# E-Book_Reader.net
KiCad netlist of a schematic drawn in EAGLE
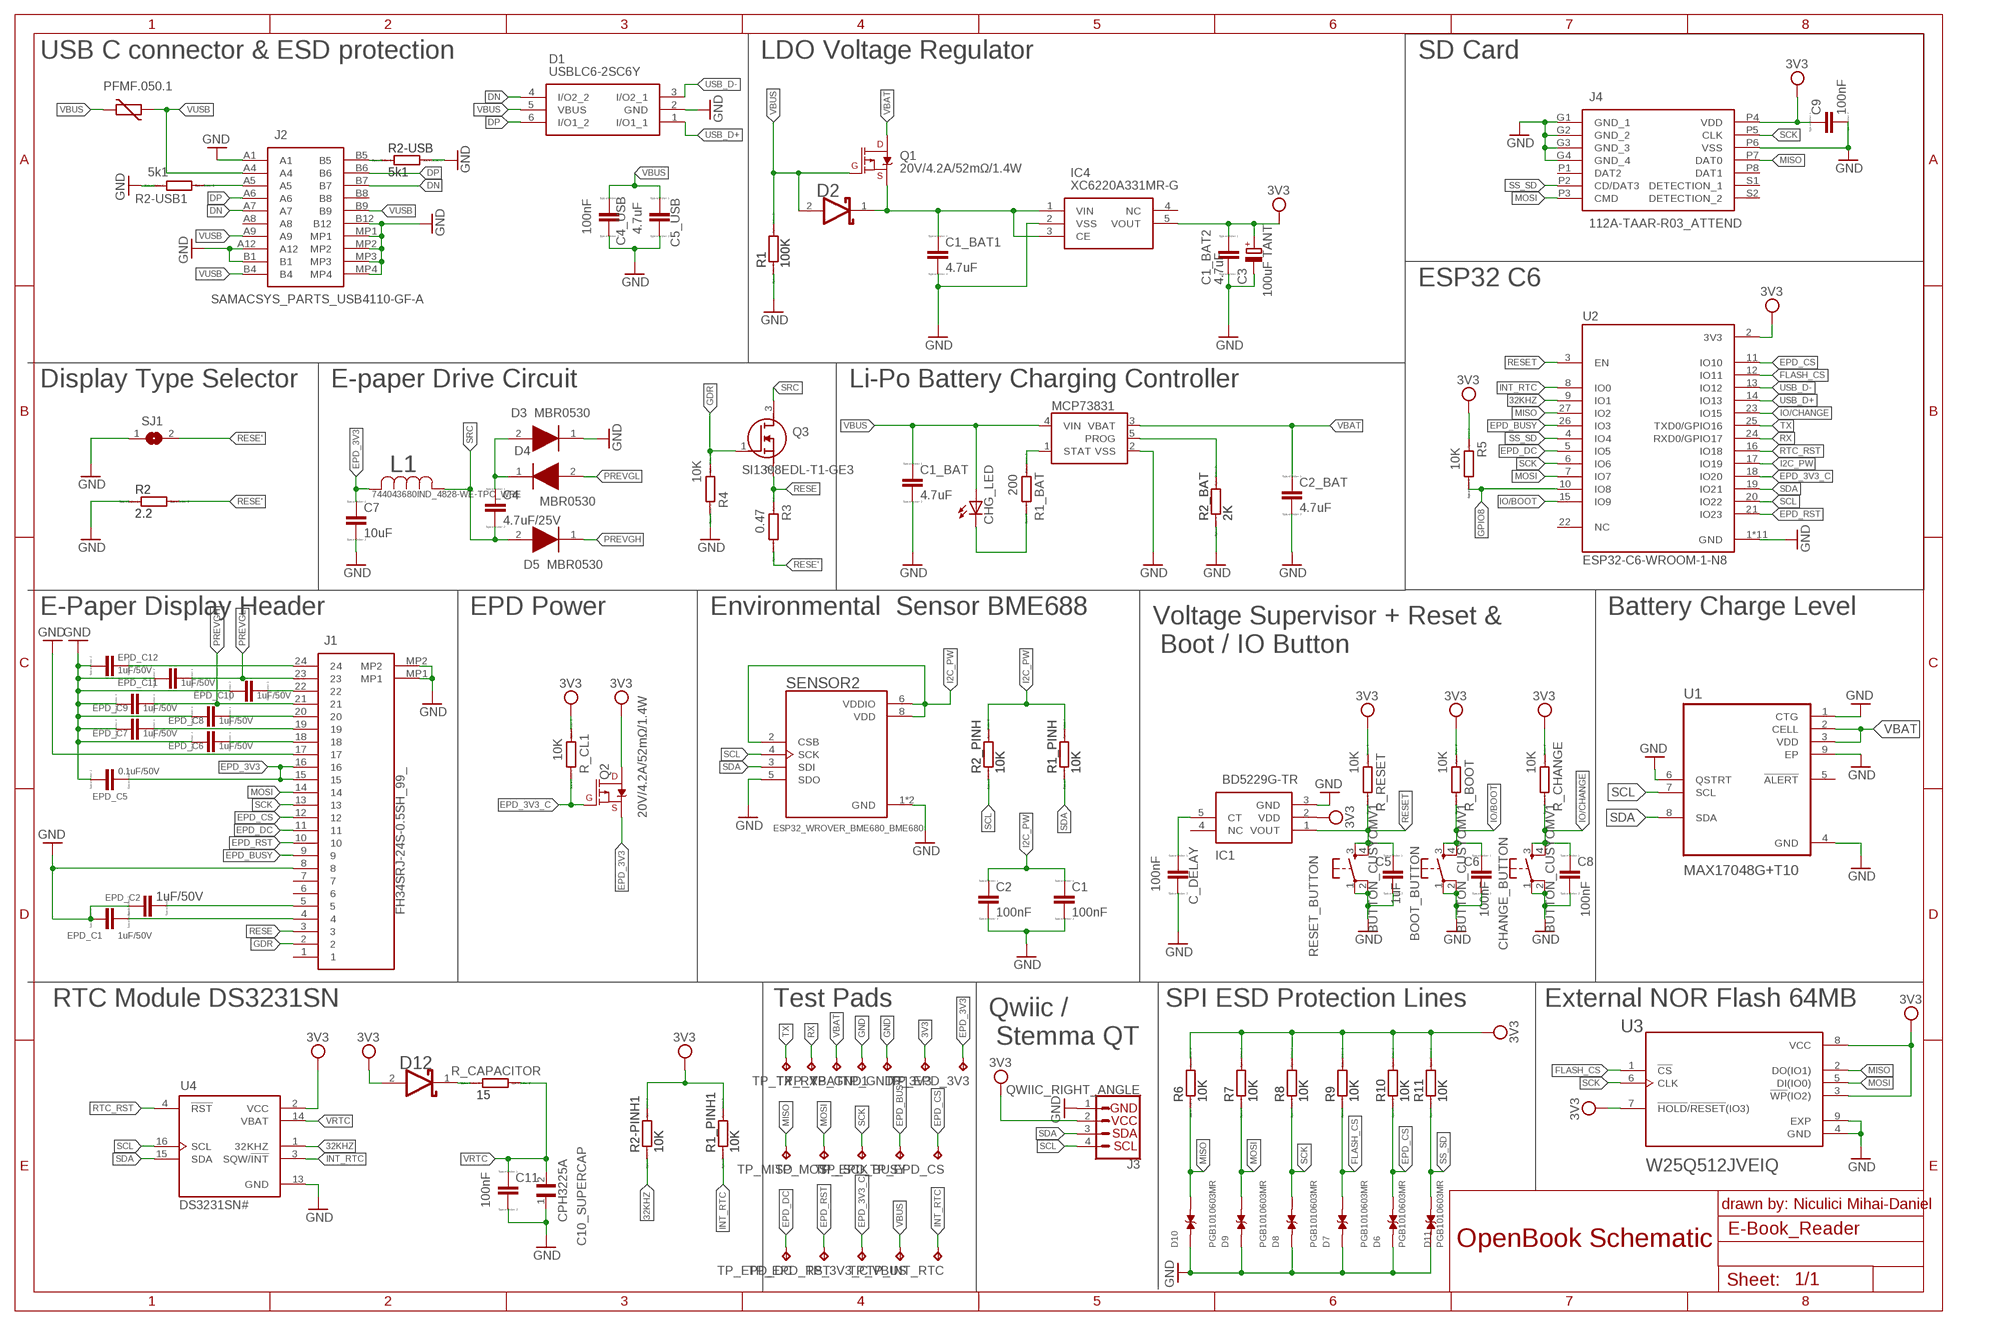
[diagram p0: schematic, sheet 1]

(export (version "E")
  (design (tool "Eeschema 10.0.6"))
  (components
    (comp (ref "BOOT_BUTTON")
      (value "BUTTON_CUSYOMV1")
      (footprint "eagle-import:MYBUTTON")
      (libsource (lib "eagle-import") (part "BUTTON_CUSYOMV1"))
    )
    (comp (ref "C1")
      (value "100nF")
      (footprint "eagle-import:ESP32_WROVER_EAGLE-LTSPICE_C0402")
      (libsource (lib "eagle-import") (part "EAGLE-LTSPICE_CC0402"))
    )
    (comp (ref "C1_BAT")
      (value "4.7uF")
      (footprint "eagle-import:ESP32_WROVER_EAGLE-LTSPICE_C0402")
      (libsource (lib "eagle-import") (part "ESP32_WROVER_EAGLE-LTSPICE_CC0402"))
    )
    (comp (ref "C1_BAT1")
      (value "4.7uF")
      (footprint "eagle-import:ESP32_WROVER_EAGLE-LTSPICE_C0402")
      (libsource (lib "eagle-import") (part "EAGLE-LTSPICE_CC0402"))
    )
    (comp (ref "C1_BAT2")
      (value "4.7uF")
      (footprint "eagle-import:ESP32_WROVER_EAGLE-LTSPICE_C0402")
      (libsource (lib "eagle-import") (part "ESP32_WROVER_EAGLE-LTSPICE_CC0402"))
    )
    (comp (ref "C2")
      (value "100nF")
      (footprint "eagle-import:ESP32_WROVER_EAGLE-LTSPICE_C0402")
      (libsource (lib "eagle-import") (part "EAGLE-LTSPICE_CC0402"))
    )
    (comp (ref "C2_BAT")
      (value "4.7uF")
      (footprint "eagle-import:ESP32_WROVER_EAGLE-LTSPICE_C0402")
      (libsource (lib "eagle-import") (part "ESP32_WROVER_EAGLE-LTSPICE_CC0402"))
    )
    (comp (ref "C3")
      (value "100uF TANT")
      (footprint "eagle-import:RCL_CT3528")
      (libsource (lib "eagle-import") (part "RCL_CPOL-EUCT3528"))
    )
    (comp (ref "C4")
      (value "4.7uF/25V")
      (footprint "eagle-import:ESP32_WROVER_EAGLE-LTSPICE_C0402")
      (libsource (lib "eagle-import") (part "ESP32_WROVER_EAGLE-LTSPICE_CC0402"))
    )
    (comp (ref "C4_USB")
      (value "100nF")
      (footprint "eagle-import:ESP32_WROVER_EAGLE-LTSPICE_C0402")
      (libsource (lib "eagle-import") (part "EAGLE-LTSPICE_CC0402"))
    )
    (comp (ref "C5")
      (value "1uF")
      (footprint "eagle-import:ESP32_WROVER_EAGLE-LTSPICE_C0402")
      (libsource (lib "eagle-import") (part "EAGLE-LTSPICE_CC0402"))
    )
    (comp (ref "C5_USB")
      (value "4.7uF")
      (footprint "eagle-import:ESP32_WROVER_EAGLE-LTSPICE_C0402")
      (libsource (lib "eagle-import") (part "EAGLE-LTSPICE_CC0402"))
    )
    (comp (ref "C6")
      (value "100nF")
      (footprint "eagle-import:ESP32_WROVER_EAGLE-LTSPICE_C0402")
      (libsource (lib "eagle-import") (part "EAGLE-LTSPICE_CC0402"))
    )
    (comp (ref "C7")
      (value "10uF")
      (footprint "eagle-import:ESP32_WROVER_EAGLE-LTSPICE_C0402")
      (libsource (lib "eagle-import") (part "EAGLE-LTSPICE_CC0402"))
    )
    (comp (ref "C8")
      (value "100nF")
      (footprint "eagle-import:ESP32_WROVER_EAGLE-LTSPICE_C0402")
      (libsource (lib "eagle-import") (part "EAGLE-LTSPICE_CC0402"))
    )
    (comp (ref "C9")
      (value "100nF")
      (footprint "eagle-import:ESP32_WROVER_EAGLE-LTSPICE_C0402")
      (libsource (lib "eagle-import") (part "EAGLE-LTSPICE_CC0402"))
    )
    (comp (ref "C10_SUPERCAP")
      (value "CPH3225A")
      (footprint "eagle-import:CAPCP3225X100N")
      (fields (field (name "MF") "Seiko Instruments"))
      (libsource (lib "eagle-import") (part "CPH3225A"))
    )
    (comp (ref "C11")
      (value "100nF")
      (footprint "eagle-import:ESP32_WROVER_EAGLE-LTSPICE_C0402")
      (libsource (lib "eagle-import") (part "EAGLE-LTSPICE_CC0402"))
    )
    (comp (ref "CHANGE_BUTTON")
      (value "BUTTON_CUSYOMV1")
      (footprint "eagle-import:MYBUTTON")
      (libsource (lib "eagle-import") (part "BUTTON_CUSYOMV1"))
    )
    (comp (ref "CHG_LED")
      (value "ADAFRUIT_LEDCHIP-LED0603")
      (footprint "eagle-import:ADAFRUIT_CHIP-LED0603")
      (libsource (lib "eagle-import") (part "ADAFRUIT_LEDCHIP-LED0603"))
    )
    (comp (ref "C_DELAY")
      (value "100nF")
      (footprint "eagle-import:ESP32_WROVER_EAGLE-LTSPICE_C0402")
      (libsource (lib "eagle-import") (part "EAGLE-LTSPICE_CC0402"))
    )
    (comp (ref "D1")
      (value "USBLC6-2SC6Y")
      (footprint "eagle-import:SOT95P280X145-6N")
      (fields (field (name "MF") "STMicroelectronics"))
      (libsource (lib "eagle-import") (part "USBLC6-2SC6Y"))
    )
    (comp (ref "D2")
      (value "ESP32_WROVER_AVX---SD0805S020S1R0_AVX_SD0805S020S1R0_0_0AVX_SD0805S020S1R0_0_0")
      (footprint "eagle-import:ESP32_WROVER_AVX---SD0805S020S1R0_AVX_SD0805S020S1R0_0")
      (fields
        (field (name "DIGIKEY_PART_NUMBER") "478-7800-1-ND")
        (field (name "MF") "AVX")
        (field (name "MOUSER_PART_NUMBER") "581-SD0805S020S1R0")
      )
      (libsource (lib "eagle-import") (part "ESP32_WROVER_AVX---SD0805S020S1R0_AVX_SD0805S020S1R0_0_0AVX_SD0805S020S1R0_0_0"))
    )
    (comp (ref "D3")
      (value "MBR0530")
      (footprint "eagle-import:SOD3716X135N")
      (fields (field (name "MF") "ON Semiconductor"))
      (libsource (lib "eagle-import") (part "MBR0530"))
    )
    (comp (ref "D4")
      (value "MBR0530")
      (footprint "eagle-import:SOD3716X135N")
      (fields (field (name "MF") "ON Semiconductor"))
      (libsource (lib "eagle-import") (part "MBR0530"))
    )
    (comp (ref "D5")
      (value "MBR0530")
      (footprint "eagle-import:SOD3716X135N")
      (fields (field (name "MF") "ON Semiconductor"))
      (libsource (lib "eagle-import") (part "MBR0530"))
    )
    (comp (ref "D6")
      (value "PGB1010603MR")
      (footprint "eagle-import:DIOC1608X36N")
      (fields (field (name "MF") "Littelfuse Inc."))
      (libsource (lib "eagle-import") (part "PGB1010603MR"))
    )
    (comp (ref "D7")
      (value "PGB1010603MR")
      (footprint "eagle-import:DIOC1608X36N")
      (fields (field (name "MF") "Littelfuse Inc."))
      (libsource (lib "eagle-import") (part "PGB1010603MR"))
    )
    (comp (ref "D8")
      (value "PGB1010603MR")
      (footprint "eagle-import:DIOC1608X36N")
      (fields (field (name "MF") "Littelfuse Inc."))
      (libsource (lib "eagle-import") (part "PGB1010603MR"))
    )
    (comp (ref "D9")
      (value "PGB1010603MR")
      (footprint "eagle-import:DIOC1608X36N")
      (fields (field (name "MF") "Littelfuse Inc."))
      (libsource (lib "eagle-import") (part "PGB1010603MR"))
    )
    (comp (ref "D10")
      (value "PGB1010603MR")
      (footprint "eagle-import:DIOC1608X36N")
      (fields (field (name "MF") "Littelfuse Inc."))
      (libsource (lib "eagle-import") (part "PGB1010603MR"))
    )
    (comp (ref "D11")
      (value "PGB1010603MR")
      (footprint "eagle-import:DIOC1608X36N")
      (fields (field (name "MF") "Littelfuse Inc."))
      (libsource (lib "eagle-import") (part "PGB1010603MR"))
    )
    (comp (ref "D12")
      (value "ESP32_WROVER_AVX---SD0805S020S1R0_AVX_SD0805S020S1R0_0_0AVX_SD0805S020S1R0_0_0")
      (footprint "eagle-import:ESP32_WROVER_AVX---SD0805S020S1R0_AVX_SD0805S020S1R0_0")
      (fields
        (field (name "DIGIKEY_PART_NUMBER") "478-7800-1-ND")
        (field (name "MF") "AVX")
        (field (name "MOUSER_PART_NUMBER") "581-SD0805S020S1R0")
      )
      (libsource (lib "eagle-import") (part "ESP32_WROVER_AVX---SD0805S020S1R0_AVX_SD0805S020S1R0_0_0AVX_SD0805S020S1R0_0_0"))
    )
    (comp (ref "EPD_C1")
      (value "1uF/50V")
      (footprint "eagle-import:ESP32_WROVER_EAGLE-LTSPICE_C0402")
      (libsource (lib "eagle-import") (part "EAGLE-LTSPICE_CC0402"))
    )
    (comp (ref "EPD_C2")
      (value "1uF/50V")
      (footprint "eagle-import:ESP32_WROVER_EAGLE-LTSPICE_C0402")
      (libsource (lib "eagle-import") (part "EAGLE-LTSPICE_CC0402"))
    )
    (comp (ref "EPD_C5")
      (value "0.1uF/50V")
      (footprint "eagle-import:ESP32_WROVER_EAGLE-LTSPICE_C0402")
      (libsource (lib "eagle-import") (part "EAGLE-LTSPICE_CC0402"))
    )
    (comp (ref "EPD_C6")
      (value "1uF/50V")
      (footprint "eagle-import:ESP32_WROVER_EAGLE-LTSPICE_C0402")
      (libsource (lib "eagle-import") (part "EAGLE-LTSPICE_CC0402"))
    )
    (comp (ref "EPD_C7")
      (value "1uF/50V")
      (footprint "eagle-import:ESP32_WROVER_EAGLE-LTSPICE_C0402")
      (libsource (lib "eagle-import") (part "EAGLE-LTSPICE_CC0402"))
    )
    (comp (ref "EPD_C8")
      (value "1uF/50V")
      (footprint "eagle-import:ESP32_WROVER_EAGLE-LTSPICE_C0402")
      (libsource (lib "eagle-import") (part "EAGLE-LTSPICE_CC0402"))
    )
    (comp (ref "EPD_C9")
      (value "1uF/50V")
      (footprint "eagle-import:ESP32_WROVER_EAGLE-LTSPICE_C0402")
      (libsource (lib "eagle-import") (part "EAGLE-LTSPICE_CC0402"))
    )
    (comp (ref "EPD_C10")
      (value "1uF/50V")
      (footprint "eagle-import:ESP32_WROVER_EAGLE-LTSPICE_C0402")
      (libsource (lib "eagle-import") (part "EAGLE-LTSPICE_CC0402"))
    )
    (comp (ref "EPD_C11")
      (value "1uF/50V")
      (footprint "eagle-import:ESP32_WROVER_EAGLE-LTSPICE_C0402")
      (libsource (lib "eagle-import") (part "EAGLE-LTSPICE_CC0402"))
    )
    (comp (ref "EPD_C12")
      (value "1uF/50V")
      (footprint "eagle-import:ESP32_WROVER_EAGLE-LTSPICE_C0402")
      (libsource (lib "eagle-import") (part "EAGLE-LTSPICE_CC0402"))
    )
    (comp (ref "IC1")
      (value "BD5229G-TR")
      (footprint "eagle-import:SOT95P280X125-5N")
      (fields (field (name "MOUSER_PART_NUMBER") "755-BD5229G-TR"))
      (libsource (lib "eagle-import") (part "BD5229G-TR"))
    )
    (comp (ref "IC4")
      (value "XC6220A331MR-G")
      (footprint "eagle-import:SOT95P280X120-5N")
      (fields (field (name "MOUSER_PART_NUMBER") "865-XC6220A331MR-G"))
      (libsource (lib "eagle-import") (part "XC6220A331MR-G"))
    )
    (comp (ref "J1")
      (value "FH34SRJ-24S-0.5SH_99_")
      (footprint "eagle-import:FH34SRJ24S05SH99")
      (fields
        (field (name "MANUFACTURER_PART_NUMBER") "FH34SRJ-24S-0.5SH(99)")
        (field (name "MOUSER_PART_NUMBER") "798-FH34SRJ24S05SH99")
      )
      (libsource (lib "eagle-import") (part "FH34SRJ-24S-0.5SH_99_"))
    )
    (comp (ref "J2")
      (value "SAMACSYS_PARTS_USB4110-GF-A")
      (footprint "eagle-import:SAMACSYS_PARTS_USB4110GFA")
      (fields
        (field (name "MANUFACTURER_PART_NUMBER") "USB4110-GF-A")
        (field (name "MOUSER_PART_NUMBER") "640-USB4110-GF-A")
      )
      (libsource (lib "eagle-import") (part "SAMACSYS_PARTS_USB4110-GF-A"))
    )
    (comp (ref "J3")
      (value "QWIIC_RIGHT_ANGLE")
      (footprint "eagle-import:JST04_1MM_RA")
      (libsource (lib "eagle-import") (part "QWIIC_CONNECTORJS-1MM"))
    )
    (comp (ref "J4")
      (value "112A-TAAR-R03_ATTEND")
      (footprint "eagle-import:112ATAARR03ATTEND")
      (fields (field (name "MANUFACTURER_PART_NUMBER") "112A-TAAR-R03 ATTEND"))
      (libsource (lib "eagle-import") (part "112A-TAAR-R03_ATTEND"))
    )
    (comp (ref "L1")
      (value "744043680IND_4828-WE-TPC_WRE")
      (footprint "eagle-import:IND_4828-WE-TPC_WRE")
      (fields
        (field (name "MANUFACTURER_PART_NUMBER") "744043680")
        (field (name "COPYRIGHT") "Copyright (C) 2024 Ultra Librarian. All rights reserved.")
      )
      (libsource (lib "eagle-import") (part "744043680IND_4828-WE-TPC_WRE"))
    )
    (comp (ref "MCP73831")
      (value "ESP32_WROVER_SPARKFUN-IC-POWER_MCP73831")
      (footprint "eagle-import:ESP32_WROVER_SPARKFUN-IC-POWER_SOT23-5")
      (libsource (lib "eagle-import") (part "ESP32_WROVER_SPARKFUN-IC-POWER_MCP73831"))
    )
    (comp (ref "PFMF.050.1")
      (value "ESP32C6_VARISTORCN1812")
      (footprint "eagle-import:ESP32C6_VARISTOR_CT_CN1812")
      (libsource (lib "eagle-import") (part "ESP32C6_VARISTORCN1812"))
    )
    (comp (ref "Q1")
      (value "20V/4.2A/52mΩ/1.4W")
      (footprint "eagle-import:ESP32_WROVER_SPARKFUN-DISCRETESEMI_SOT23-3")
      (libsource (lib "eagle-import") (part "ESP32_WROVER_SPARKFUN-DISCRETESEMI_MOSFET_PCH-DMG2305UX-7"))
    )
    (comp (ref "Q2")
      (value "20V/4.2A/52mΩ/1.4W")
      (footprint "eagle-import:ESP32_WROVER_SPARKFUN-DISCRETESEMI_SOT23-3")
      (libsource (lib "eagle-import") (part "ESP32_WROVER_SPARKFUN-DISCRETESEMI_MOSFET_PCH-DMG2305UX-7"))
    )
    (comp (ref "Q3")
      (value "SI1308EDL-T1-GE3")
      (footprint "eagle-import:SOT65P210X110-3N")
      (fields (field (name "MF") "Vishay Siliconix"))
      (libsource (lib "eagle-import") (part "SI1308EDL-T1-GE3"))
    )
    (comp (ref "R1")
      (value "100K")
      (footprint "eagle-import:ESP32_WROVER_EAGLE-LTSPICE_R0402")
      (libsource (lib "eagle-import") (part "ESP32_WROVER_EAGLE-LTSPICE_RR0402"))
    )
    (comp (ref "R1_BAT")
      (value "200")
      (footprint "eagle-import:ESP32_WROVER_EAGLE-LTSPICE_R0402")
      (libsource (lib "eagle-import") (part "ESP32_WROVER_EAGLE-LTSPICE_RR0402"))
    )
    (comp (ref "R1_PINH")
      (value "10K")
      (footprint "eagle-import:ESP32_WROVER_EAGLE-LTSPICE_R0402")
      (libsource (lib "eagle-import") (part "ESP32_WROVER_EAGLE-LTSPICE_RR0402"))
    )
    (comp (ref "R1_PINH1")
      (value "10K")
      (footprint "eagle-import:ESP32_WROVER_EAGLE-LTSPICE_R0402")
      (libsource (lib "eagle-import") (part "ESP32_WROVER_EAGLE-LTSPICE_RR0402"))
    )
    (comp (ref "R2")
      (value "2.2")
      (footprint "eagle-import:ESP32_WROVER_EAGLE-LTSPICE_R0402")
      (libsource (lib "eagle-import") (part "ESP32_WROVER_EAGLE-LTSPICE_RR0402"))
    )
    (comp (ref "R2-PINH1")
      (value "10K")
      (footprint "eagle-import:ESP32_WROVER_EAGLE-LTSPICE_R0402")
      (libsource (lib "eagle-import") (part "ESP32_WROVER_EAGLE-LTSPICE_RR0402"))
    )
    (comp (ref "R2-USB")
      (value "5k1")
      (footprint "eagle-import:ESP32_WROVER_EAGLE-LTSPICE_R0402")
      (libsource (lib "eagle-import") (part "ESP32_WROVER_EAGLE-LTSPICE_RR0402"))
    )
    (comp (ref "R2-USB1")
      (value "5k1")
      (footprint "eagle-import:ESP32_WROVER_EAGLE-LTSPICE_R0402")
      (libsource (lib "eagle-import") (part "ESP32_WROVER_EAGLE-LTSPICE_RR0402"))
    )
    (comp (ref "R2_BAT")
      (value "2K")
      (footprint "eagle-import:ESP32_WROVER_EAGLE-LTSPICE_R0402")
      (libsource (lib "eagle-import") (part "ESP32_WROVER_EAGLE-LTSPICE_RR0402"))
    )
    (comp (ref "R2_PINH")
      (value "10K")
      (footprint "eagle-import:ESP32_WROVER_EAGLE-LTSPICE_R0402")
      (libsource (lib "eagle-import") (part "ESP32_WROVER_EAGLE-LTSPICE_RR0402"))
    )
    (comp (ref "R3")
      (value "0.47")
      (footprint "eagle-import:ESP32_WROVER_EAGLE-LTSPICE_R0402")
      (libsource (lib "eagle-import") (part "ESP32_WROVER_EAGLE-LTSPICE_RR0402"))
    )
    (comp (ref "R4")
      (value "10K")
      (footprint "eagle-import:ESP32_WROVER_EAGLE-LTSPICE_R0402")
      (libsource (lib "eagle-import") (part "ESP32_WROVER_EAGLE-LTSPICE_RR0402"))
    )
    (comp (ref "R5")
      (value "10K")
      (footprint "eagle-import:ESP32_WROVER_EAGLE-LTSPICE_R0402")
      (libsource (lib "eagle-import") (part "ESP32_WROVER_EAGLE-LTSPICE_RR0402"))
    )
    (comp (ref "R6")
      (value "10K")
      (footprint "eagle-import:ESP32_WROVER_EAGLE-LTSPICE_R0402")
      (libsource (lib "eagle-import") (part "ESP32_WROVER_EAGLE-LTSPICE_RR0402"))
    )
    (comp (ref "R7")
      (value "10K")
      (footprint "eagle-import:ESP32_WROVER_EAGLE-LTSPICE_R0402")
      (libsource (lib "eagle-import") (part "ESP32_WROVER_EAGLE-LTSPICE_RR0402"))
    )
    (comp (ref "R8")
      (value "10K")
      (footprint "eagle-import:ESP32_WROVER_EAGLE-LTSPICE_R0402")
      (libsource (lib "eagle-import") (part "ESP32_WROVER_EAGLE-LTSPICE_RR0402"))
    )
    (comp (ref "R9")
      (value "10K")
      (footprint "eagle-import:ESP32_WROVER_EAGLE-LTSPICE_R0402")
      (libsource (lib "eagle-import") (part "ESP32_WROVER_EAGLE-LTSPICE_RR0402"))
    )
    (comp (ref "R10")
      (value "10K")
      (footprint "eagle-import:ESP32_WROVER_EAGLE-LTSPICE_R0402")
      (libsource (lib "eagle-import") (part "ESP32_WROVER_EAGLE-LTSPICE_RR0402"))
    )
    (comp (ref "R11")
      (value "10K")
      (footprint "eagle-import:ESP32_WROVER_EAGLE-LTSPICE_R0402")
      (libsource (lib "eagle-import") (part "ESP32_WROVER_EAGLE-LTSPICE_RR0402"))
    )
    (comp (ref "RESET_BUTTON")
      (value "BUTTON_CUSYOMV1")
      (footprint "eagle-import:MYBUTTON")
      (libsource (lib "eagle-import") (part "BUTTON_CUSYOMV1"))
    )
    (comp (ref "R_BOOT")
      (value "10K")
      (footprint "eagle-import:ESP32_WROVER_EAGLE-LTSPICE_R0402")
      (libsource (lib "eagle-import") (part "ESP32_WROVER_EAGLE-LTSPICE_RR0402"))
    )
    (comp (ref "R_CAPACITOR")
      (value "15")
      (footprint "eagle-import:ESP32_WROVER_EAGLE-LTSPICE_R0402")
      (libsource (lib "eagle-import") (part "ESP32_WROVER_EAGLE-LTSPICE_RR0402"))
    )
    (comp (ref "R_CHANGE")
      (value "10K")
      (footprint "eagle-import:ESP32_WROVER_EAGLE-LTSPICE_R0402")
      (libsource (lib "eagle-import") (part "ESP32_WROVER_EAGLE-LTSPICE_RR0402"))
    )
    (comp (ref "R_CL1")
      (value "10K")
      (footprint "eagle-import:ESP32_WROVER_EAGLE-LTSPICE_R0402")
      (libsource (lib "eagle-import") (part "ESP32_WROVER_EAGLE-LTSPICE_RR0402"))
    )
    (comp (ref "R_RESET")
      (value "10K")
      (footprint "eagle-import:ESP32_WROVER_EAGLE-LTSPICE_R0402")
      (libsource (lib "eagle-import") (part "ESP32_WROVER_EAGLE-LTSPICE_RR0402"))
    )
    (comp (ref "SENSOR2")
      (value "ESP32_WROVER_BME680_BME680")
      (footprint "eagle-import:ESP32_WROVER_BME680_PSON80P300X300X100-8N")
      (fields (field (name "MF") "Bosch Sensortec") (field (name "MP") "BME680"))
      (libsource (lib "eagle-import") (part "ESP32_WROVER_BME680_BME680"))
    )
    (comp (ref "SJ1") (value "SJ") (footprint "eagle-import:SJ") (libsource (lib "eagle-import") (part "SJ")))
    (comp (ref "TP_3V3")
      (value "TPTP20R")
      (footprint "eagle-import:TP20R")
      (libsource (lib "eagle-import") (part "TPTP20R"))
    )
    (comp (ref "TP_3V3_C")
      (value "TPTP20R")
      (footprint "eagle-import:TP20R")
      (libsource (lib "eagle-import") (part "TPTP20R"))
    )
    (comp (ref "TP_EPD_3V3")
      (value "TPTP20R")
      (footprint "eagle-import:TP20R")
      (libsource (lib "eagle-import") (part "TPTP20R"))
    )
    (comp (ref "TP_EPD_BUSY")
      (value "TPTP20R")
      (footprint "eagle-import:TP20R")
      (libsource (lib "eagle-import") (part "TPTP20R"))
    )
    (comp (ref "TP_EPD_CS")
      (value "TPTP20R")
      (footprint "eagle-import:TP20R")
      (libsource (lib "eagle-import") (part "TPTP20R"))
    )
    (comp (ref "TP_EPD_DC")
      (value "TPTP20R")
      (footprint "eagle-import:TP20R")
      (libsource (lib "eagle-import") (part "TPTP20R"))
    )
    (comp (ref "TP_EPD_RST")
      (value "TPTP20R")
      (footprint "eagle-import:TP20R")
      (libsource (lib "eagle-import") (part "TPTP20R"))
    )
    (comp (ref "TP_GND")
      (value "TPTP20R")
      (footprint "eagle-import:TP20R")
      (libsource (lib "eagle-import") (part "TPTP20R"))
    )
    (comp (ref "TP_GND1")
      (value "TPTP20R")
      (footprint "eagle-import:TP20R")
      (libsource (lib "eagle-import") (part "TPTP20R"))
    )
    (comp (ref "TP_INT_RTC")
      (value "TPTP20R")
      (footprint "eagle-import:TP20R")
      (libsource (lib "eagle-import") (part "TPTP20R"))
    )
    (comp (ref "TP_MISO")
      (value "TPTP20R")
      (footprint "eagle-import:TP20R")
      (libsource (lib "eagle-import") (part "TPTP20R"))
    )
    (comp (ref "TP_MOSI")
      (value "TPTP20R")
      (footprint "eagle-import:TP20R")
      (libsource (lib "eagle-import") (part "TPTP20R"))
    )
    (comp (ref "TP_RX")
      (value "TPTP20R")
      (footprint "eagle-import:TP20R")
      (libsource (lib "eagle-import") (part "TPTP20R"))
    )
    (comp (ref "TP_SCK")
      (value "TPTP20R")
      (footprint "eagle-import:TP20R")
      (libsource (lib "eagle-import") (part "TPTP20R"))
    )
    (comp (ref "TP_TX")
      (value "TPTP20R")
      (footprint "eagle-import:TP20R")
      (libsource (lib "eagle-import") (part "TPTP20R"))
    )
    (comp (ref "TP_VBAT")
      (value "TPTP20R")
      (footprint "eagle-import:TP20R")
      (libsource (lib "eagle-import") (part "TPTP20R"))
    )
    (comp (ref "TP_VBUS")
      (value "TPTP20R")
      (footprint "eagle-import:TP20R")
      (libsource (lib "eagle-import") (part "TPTP20R"))
    )
    (comp (ref "U1")
      (value "MAX17048G+T10")
      (footprint "eagle-import:SON50P200X200X80-9N")
      (fields (field (name "MF") "Analog Devices"))
      (libsource (lib "eagle-import") (part "MAX17048G+T10"))
    )
    (comp (ref "U2")
      (value "ESP32-C6-WROOM-1-N8")
      (footprint "eagle-import:XCVR_ESP32-C6-WROOM-1-N8")
      (fields (field (name "MF") "Espressif Systems"))
      (libsource (lib "eagle-import") (part "ESP32-C6-WROOM-1-N8"))
    )
    (comp (ref "U3")
      (value "W25Q512JVEIQ")
      (footprint "eagle-import:SON127P600X800X80-9N")
      (fields (field (name "MF") "Winbond Electronics"))
      (libsource (lib "eagle-import") (part "W25Q512JVEIQ"))
    )
    (comp (ref "U4")
      (value "DS3231SN#")
      (footprint "eagle-import:SOIC127P1032X265-16N")
      (fields (field (name "MF") "Analog Devices"))
      (libsource (lib "eagle-import") (part "DS3231SN#"))
    )
  )
  (nets
    (net (code "1") (name "3V3") (class "Default")
      (node (ref "C1_BAT2") (pin "1") (pinfunction "1_1") (pintype "passive"))
      (node (ref "C3") (pin "+") (pinfunction "+_+") (pintype "passive"))
      (node (ref "C9") (pin "1") (pinfunction "1_1") (pintype "passive"))
      (node (ref "D12") (pin "2") (pinfunction "ANODE_2") (pintype "bidirectional"))
      (node (ref "IC1") (pin "2") (pinfunction "VDD_2") (pintype "bidirectional"))
      (node (ref "IC4") (pin "5") (pinfunction "VOUT_5") (pintype "bidirectional"))
      (node (ref "J3") (pin "2") (pinfunction "2_2") (pintype "power_in"))
      (node (ref "J4") (pin "P4") (pinfunction "VDD_P4") (pintype "bidirectional"))
      (node (ref "Q2") (pin "3") (pinfunction "D_3") (pintype "bidirectional"))
      (node (ref "R10") (pin "2") (pinfunction "2_2") (pintype "passive"))
      (node (ref "R11") (pin "2") (pinfunction "2_2") (pintype "passive"))
      (node (ref "R1_PINH1") (pin "2") (pinfunction "2_2") (pintype "passive"))
      (node (ref "R2-PINH1") (pin "2") (pinfunction "2_2") (pintype "passive"))
      (node (ref "R5") (pin "2") (pinfunction "2_2") (pintype "passive"))
      (node (ref "R6") (pin "2") (pinfunction "2_2") (pintype "passive"))
      (node (ref "R7") (pin "2") (pinfunction "2_2") (pintype "passive"))
      (node (ref "R8") (pin "2") (pinfunction "2_2") (pintype "passive"))
      (node (ref "R9") (pin "2") (pinfunction "2_2") (pintype "passive"))
      (node (ref "R_BOOT") (pin "2") (pinfunction "2_2") (pintype "passive"))
      (node (ref "R_CHANGE") (pin "2") (pinfunction "2_2") (pintype "passive"))
      (node (ref "R_CL1") (pin "2") (pinfunction "2_2") (pintype "passive"))
      (node (ref "R_RESET") (pin "2") (pinfunction "2_2") (pintype "passive"))
      (node (ref "TP_3V3") (pin "TP") (pinfunction "TP_TP") (pintype "input"))
      (node (ref "U2") (pin "2") (pinfunction "3V3_2") (pintype "power_in"))
      (node (ref "U3") (pin "3") (pinfunction "~{WP}(IO2)_3") (pintype "bidirectional"))
      (node (ref "U3") (pin "7") (pinfunction "~{HOLD}/~{RESET}(IO3)_7") (pintype "bidirectional"))
      (node (ref "U3") (pin "8") (pinfunction "VCC_8") (pintype "power_in"))
      (node (ref "U4") (pin "2") (pinfunction "VCC_2") (pintype "power_in"))
    )
    (net (code "2") (name "32KHZ") (class "Default")
      (node (ref "R2-PINH1") (pin "1") (pinfunction "1_1") (pintype "passive"))
      (node (ref "U2") (pin "9") (pinfunction "IO1_9") (pintype "bidirectional"))
      (node (ref "U4") (pin "1") (pinfunction "32KHZ_1") (pintype "output"))
    )
    (net (code "3") (name "DN") (class "Default")
      (node (ref "D1") (pin "4") (pinfunction "I/O2_2_4") (pintype "bidirectional"))
      (node (ref "J2") (pin "A7") (pinfunction "A7_A7") (pintype "bidirectional"))
      (node (ref "J2") (pin "B7") (pinfunction "B7_B7") (pintype "bidirectional"))
    )
    (net (code "4") (name "DP") (class "Default")
      (node (ref "D1") (pin "6") (pinfunction "I/O1_2_6") (pintype "bidirectional"))
      (node (ref "J2") (pin "A6") (pinfunction "A6_A6") (pintype "bidirectional"))
      (node (ref "J2") (pin "B6") (pinfunction "B6_B6") (pintype "bidirectional"))
    )
    (net (code "5") (name "EPD_3V3") (class "Default")
      (node (ref "C7") (pin "1") (pinfunction "1_1") (pintype "passive"))
      (node (ref "EPD_C5") (pin "1") (pinfunction "1_1") (pintype "passive"))
      (node (ref "J1") (pin "15") (pinfunction "15_15") (pintype "bidirectional"))
      (node (ref "J1") (pin "16") (pinfunction "16_16") (pintype "bidirectional"))
      (node (ref "L1") (pin "2") (pinfunction "2_2") (pintype "passive"))
      (node (ref "Q2") (pin "2") (pinfunction "S_2") (pintype "bidirectional"))
      (node (ref "TP_EPD_3V3") (pin "TP") (pinfunction "TP_TP") (pintype "input"))
    )
    (net (code "6") (name "EPD_3V3_C") (class "Default")
      (node (ref "Q2") (pin "1") (pinfunction "G_1") (pintype "bidirectional"))
      (node (ref "R_CL1") (pin "1") (pinfunction "1_1") (pintype "passive"))
      (node (ref "TP_3V3_C") (pin "TP") (pinfunction "TP_TP") (pintype "input"))
      (node (ref "U2") (pin "18") (pinfunction "IO20_18") (pintype "bidirectional"))
    )
    (net (code "7") (name "EPD_BUSY") (class "Default")
      (node (ref "J1") (pin "9") (pinfunction "9_9") (pintype "bidirectional"))
      (node (ref "TP_EPD_BUSY") (pin "TP") (pinfunction "TP_TP") (pintype "input"))
      (node (ref "U2") (pin "26") (pinfunction "IO3_26") (pintype "bidirectional"))
    )
    (net (code "8") (name "EPD_CS") (class "Default")
      (node (ref "D6") (pin "2") (pinfunction "2_2") (pintype "passive"))
      (node (ref "J1") (pin "12") (pinfunction "12_12") (pintype "bidirectional"))
      (node (ref "R10") (pin "1") (pinfunction "1_1") (pintype "passive"))
      (node (ref "TP_EPD_CS") (pin "TP") (pinfunction "TP_TP") (pintype "input"))
      (node (ref "U2") (pin "11") (pinfunction "IO10_11") (pintype "bidirectional"))
    )
    (net (code "9") (name "EPD_DC") (class "Default")
      (node (ref "J1") (pin "11") (pinfunction "11_11") (pintype "bidirectional"))
      (node (ref "TP_EPD_DC") (pin "TP") (pinfunction "TP_TP") (pintype "input"))
      (node (ref "U2") (pin "5") (pinfunction "IO5_5") (pintype "bidirectional"))
    )
    (net (code "10") (name "EPD_RST") (class "Default")
      (node (ref "J1") (pin "10") (pinfunction "10_10") (pintype "bidirectional"))
      (node (ref "TP_EPD_RST") (pin "TP") (pinfunction "TP_TP") (pintype "input"))
      (node (ref "U2") (pin "21") (pinfunction "IO23_21") (pintype "bidirectional"))
    )
    (net (code "11") (name "FLASH_CS") (class "Default")
      (node (ref "D7") (pin "2") (pinfunction "2_2") (pintype "passive"))
      (node (ref "R9") (pin "1") (pinfunction "1_1") (pintype "passive"))
      (node (ref "U2") (pin "12") (pinfunction "IO11_12") (pintype "bidirectional"))
      (node (ref "U3") (pin "1") (pinfunction "~{CS}_1") (pintype "input"))
    )
    (net (code "12") (name "GDR") (class "Default")
      (node (ref "J1") (pin "2") (pinfunction "2_2") (pintype "bidirectional"))
      (node (ref "Q3") (pin "1") (pinfunction "G_1") (pintype "bidirectional"))
      (node (ref "R4") (pin "2") (pinfunction "2_2") (pintype "passive"))
    )
    (net (code "13") (name "GND") (class "Default")
      (node (ref "BOOT_BUTTON") (pin "1") (pinfunction "1_1") (pintype "passive"))
      (node (ref "BOOT_BUTTON") (pin "2") (pinfunction "2_2") (pintype "passive"))
      (node (ref "C1") (pin "2") (pinfunction "2_2") (pintype "passive"))
      (node (ref "C10_SUPERCAP") (pin "1") (pinfunction "1_1") (pintype "passive"))
      (node (ref "C11") (pin "2") (pinfunction "2_2") (pintype "passive"))
      (node (ref "C1_BAT") (pin "2") (pinfunction "2_2") (pintype "passive"))
      (node (ref "C1_BAT1") (pin "2") (pinfunction "2_2") (pintype "passive"))
      (node (ref "C1_BAT2") (pin "2") (pinfunction "2_2") (pintype "passive"))
      (node (ref "C2") (pin "2") (pinfunction "2_2") (pintype "passive"))
      (node (ref "C2_BAT") (pin "2") (pinfunction "2_2") (pintype "passive"))
      (node (ref "C3") (pin "-") (pinfunction "-_-") (pintype "passive"))
      (node (ref "C4_USB") (pin "2") (pinfunction "2_2") (pintype "passive"))
      (node (ref "C5") (pin "2") (pinfunction "2_2") (pintype "passive"))
      (node (ref "C5_USB") (pin "2") (pinfunction "2_2") (pintype "passive"))
      (node (ref "C6") (pin "2") (pinfunction "2_2") (pintype "passive"))
      (node (ref "C7") (pin "2") (pinfunction "2_2") (pintype "passive"))
      (node (ref "C8") (pin "2") (pinfunction "2_2") (pintype "passive"))
      (node (ref "C9") (pin "2") (pinfunction "2_2") (pintype "passive"))
      (node (ref "CHANGE_BUTTON") (pin "1") (pinfunction "1_1") (pintype "passive"))
      (node (ref "CHANGE_BUTTON") (pin "2") (pinfunction "2_2") (pintype "passive"))
      (node (ref "C_DELAY") (pin "2") (pinfunction "2_2") (pintype "passive"))
      (node (ref "D1") (pin "2") (pinfunction "GND_2") (pintype "bidirectional"))
      (node (ref "D10") (pin "1") (pinfunction "1_1") (pintype "passive"))
      (node (ref "D11") (pin "1") (pinfunction "1_1") (pintype "passive"))
      (node (ref "D3") (pin "1") (pinfunction "K_1") (pintype "bidirectional"))
      (node (ref "D6") (pin "1") (pinfunction "1_1") (pintype "passive"))
      (node (ref "D7") (pin "1") (pinfunction "1_1") (pintype "passive"))
      (node (ref "D8") (pin "1") (pinfunction "1_1") (pintype "passive"))
      (node (ref "D9") (pin "1") (pinfunction "1_1") (pintype "passive"))
      (node (ref "EPD_C1") (pin "2") (pinfunction "2_2") (pintype "passive"))
      (node (ref "EPD_C10") (pin "2") (pinfunction "2_2") (pintype "passive"))
      (node (ref "EPD_C11") (pin "2") (pinfunction "2_2") (pintype "passive"))
      (node (ref "EPD_C12") (pin "2") (pinfunction "2_2") (pintype "passive"))
      (node (ref "EPD_C2") (pin "2") (pinfunction "2_2") (pintype "passive"))
      (node (ref "EPD_C5") (pin "2") (pinfunction "2_2") (pintype "passive"))
      (node (ref "EPD_C6") (pin "2") (pinfunction "2_2") (pintype "passive"))
      (node (ref "EPD_C7") (pin "2") (pinfunction "2_2") (pintype "passive"))
      (node (ref "EPD_C8") (pin "2") (pinfunction "2_2") (pintype "passive"))
      (node (ref "EPD_C9") (pin "2") (pinfunction "2_2") (pintype "passive"))
      (node (ref "IC1") (pin "3") (pinfunction "GND_3") (pintype "bidirectional"))
      (node (ref "IC4") (pin "2") (pinfunction "VSS_2") (pintype "bidirectional"))
      (node (ref "J1") (pin "17") (pinfunction "17_17") (pintype "bidirectional"))
      (node (ref "J1") (pin "8") (pinfunction "8_8") (pintype "bidirectional"))
      (node (ref "J1") (pin "MP1") (pinfunction "MP1_MP1") (pintype "bidirectional"))
      (node (ref "J1") (pin "MP2") (pinfunction "MP2_MP2") (pintype "bidirectional"))
      (node (ref "J2") (pin "A1") (pinfunction "A1_A1") (pintype "bidirectional"))
      (node (ref "J2") (pin "A12") (pinfunction "A12_A12") (pintype "bidirectional"))
      (node (ref "J2") (pin "B1") (pinfunction "B1_B1") (pintype "bidirectional"))
      (node (ref "J2") (pin "B12") (pinfunction "B12_B12") (pintype "bidirectional"))
      (node (ref "J2") (pin "MP1") (pinfunction "MP1_MP1") (pintype "bidirectional"))
      (node (ref "J2") (pin "MP2") (pinfunction "MP2_MP2") (pintype "bidirectional"))
      (node (ref "J2") (pin "MP3") (pinfunction "MP3_MP3") (pintype "bidirectional"))
      (node (ref "J2") (pin "MP4") (pinfunction "MP4_MP4") (pintype "bidirectional"))
      (node (ref "J3") (pin "1") (pinfunction "1_1") (pintype "power_in"))
      (node (ref "J4") (pin "G1") (pinfunction "GND_1_G1") (pintype "bidirectional"))
      (node (ref "J4") (pin "G2") (pinfunction "GND_2_G2") (pintype "bidirectional"))
      (node (ref "J4") (pin "G3") (pinfunction "GND_3_G3") (pintype "bidirectional"))
      (node (ref "J4") (pin "G4") (pinfunction "GND_4_G4") (pintype "bidirectional"))
      (node (ref "J4") (pin "P6") (pinfunction "VSS_P6") (pintype "bidirectional"))
      (node (ref "MCP73831") (pin "2") (pinfunction "VSS_2") (pintype "power_in"))
      (node (ref "R1") (pin "1") (pinfunction "1_1") (pintype "passive"))
      (node (ref "R2") (pin "1") (pinfunction "1_1") (pintype "passive"))
      (node (ref "R2-USB") (pin "2") (pinfunction "2_2") (pintype "passive"))
      (node (ref "R2-USB1") (pin "1") (pinfunction "1_1") (pintype "passive"))
      (node (ref "R2_BAT") (pin "1") (pinfunction "1_1") (pintype "passive"))
      (node (ref "R4") (pin "1") (pinfunction "1_1") (pintype "passive"))
      (node (ref "RESET_BUTTON") (pin "1") (pinfunction "1_1") (pintype "passive"))
      (node (ref "RESET_BUTTON") (pin "2") (pinfunction "2_2") (pintype "passive"))
      (node (ref "SENSOR2") (pin "1") (pinfunction "GND_1") (pintype "power_in"))
      (node (ref "SENSOR2") (pin "5") (pinfunction "SDO_5") (pintype "bidirectional"))
      (node (ref "SENSOR2") (pin "7") (pinfunction "GND_7") (pintype "power_in"))
      (node (ref "SJ1") (pin "1") (pinfunction "1_1") (pintype "passive"))
      (node (ref "TP_GND") (pin "TP") (pinfunction "TP_TP") (pintype "input"))
      (node (ref "TP_GND1") (pin "TP") (pinfunction "TP_TP") (pintype "input"))
      (node (ref "U1") (pin "1") (pinfunction "CTG_1") (pintype "power_in"))
      (node (ref "U1") (pin "4") (pinfunction "GND_4") (pintype "power_in"))
      (node (ref "U1") (pin "6") (pinfunction "QSTRT_6") (pintype "input"))
      (node (ref "U1") (pin "9") (pinfunction "EP_9") (pintype "power_in"))
      (node (ref "U2") (pin "1") (pinfunction "GND_1") (pintype "power_in"))
      (node (ref "U2") (pin "28") (pinfunction "GND_28") (pintype "power_in"))
      (node (ref "U2") (pin "29_1") (pinfunction "GND_29_1") (pintype "power_in"))
      (node (ref "U2") (pin "29_2") (pinfunction "GND_29_2") (pintype "power_in"))
      (node (ref "U2") (pin "29_3") (pinfunction "GND_29_3") (pintype "power_in"))
      (node (ref "U2") (pin "29_4") (pinfunction "GND_29_4") (pintype "power_in"))
      (node (ref "U2") (pin "29_5") (pinfunction "GND_29_5") (pintype "power_in"))
      (node (ref "U2") (pin "29_6") (pinfunction "GND_29_6") (pintype "power_in"))
      (node (ref "U2") (pin "29_7") (pinfunction "GND_29_7") (pintype "power_in"))
      (node (ref "U2") (pin "29_8") (pinfunction "GND_29_8") (pintype "power_in"))
      (node (ref "U2") (pin "29_9") (pinfunction "GND_29_9") (pintype "power_in"))
      (node (ref "U3") (pin "4") (pinfunction "GND_4") (pintype "power_in"))
      (node (ref "U3") (pin "9") (pinfunction "EXP_9") (pintype "passive"))
      (node (ref "U4") (pin "13") (pinfunction "GND_13") (pintype "power_in"))
    )
    (net (code "14") (name "GPIO8") (class "Default")
      (node (ref "R5") (pin "1") (pinfunction "1_1") (pintype "passive"))
      (node (ref "U2") (pin "10") (pinfunction "IO8_10") (pintype "bidirectional"))
    )
    (net (code "15") (name "I2C_PW") (class "Default")
      (node (ref "C1") (pin "1") (pinfunction "1_1") (pintype "passive"))
      (node (ref "C2") (pin "1") (pinfunction "1_1") (pintype "passive"))
      (node (ref "R1_PINH") (pin "2") (pinfunction "2_2") (pintype "passive"))
      (node (ref "R2_PINH") (pin "2") (pinfunction "2_2") (pintype "passive"))
      (node (ref "SENSOR2") (pin "2") (pinfunction "CSB_2") (pintype "input"))
      (node (ref "SENSOR2") (pin "6") (pinfunction "VDDIO_6") (pintype "power_in"))
      (node (ref "SENSOR2") (pin "8") (pinfunction "VDD_8") (pintype "power_in"))
      (node (ref "U2") (pin "17") (pinfunction "IO19_17") (pintype "bidirectional"))
    )
    (net (code "16") (name "INT_RTC") (class "Default")
      (node (ref "R1_PINH1") (pin "1") (pinfunction "1_1") (pintype "passive"))
      (node (ref "TP_INT_RTC") (pin "TP") (pinfunction "TP_TP") (pintype "input"))
      (node (ref "U2") (pin "8") (pinfunction "IO0_8") (pintype "bidirectional"))
      (node (ref "U4") (pin "3") (pinfunction "SQW/~{INT}_3") (pintype "output"))
    )
    (net (code "17") (name "IO{slash}BOOT") (class "Default")
      (node (ref "BOOT_BUTTON") (pin "3") (pinfunction "3_3") (pintype "passive"))
      (node (ref "BOOT_BUTTON") (pin "4") (pinfunction "4_4") (pintype "passive"))
      (node (ref "C6") (pin "1") (pinfunction "1_1") (pintype "passive"))
      (node (ref "R_BOOT") (pin "1") (pinfunction "1_1") (pintype "passive"))
      (node (ref "U2") (pin "15") (pinfunction "IO9_15") (pintype "bidirectional"))
    )
    (net (code "18") (name "IO{slash}CHANGE") (class "Default")
      (node (ref "C8") (pin "1") (pinfunction "1_1") (pintype "passive"))
      (node (ref "CHANGE_BUTTON") (pin "3") (pinfunction "3_3") (pintype "passive"))
      (node (ref "CHANGE_BUTTON") (pin "4") (pinfunction "4_4") (pintype "passive"))
      (node (ref "R_CHANGE") (pin "1") (pinfunction "1_1") (pintype "passive"))
      (node (ref "U2") (pin "23") (pinfunction "IO15_23") (pintype "bidirectional"))
    )
    (net (code "19") (name "MISO") (class "Default")
      (node (ref "D10") (pin "2") (pinfunction "2_2") (pintype "passive"))
      (node (ref "J4") (pin "P7") (pinfunction "DAT0_P7") (pintype "bidirectional"))
      (node (ref "R6") (pin "1") (pinfunction "1_1") (pintype "passive"))
      (node (ref "TP_MISO") (pin "TP") (pinfunction "TP_TP") (pintype "input"))
      (node (ref "U2") (pin "27") (pinfunction "IO2_27") (pintype "bidirectional"))
      (node (ref "U3") (pin "2") (pinfunction "DO(IO1)_2") (pintype "bidirectional"))
    )
    (net (code "20") (name "MOSI") (class "Default")
      (node (ref "D9") (pin "2") (pinfunction "2_2") (pintype "passive"))
      (node (ref "J1") (pin "14") (pinfunction "14_14") (pintype "bidirectional"))
      (node (ref "J4") (pin "P3") (pinfunction "CMD_P3") (pintype "bidirectional"))
      (node (ref "R7") (pin "1") (pinfunction "1_1") (pintype "passive"))
      (node (ref "TP_MOSI") (pin "TP") (pinfunction "TP_TP") (pintype "input"))
      (node (ref "U2") (pin "7") (pinfunction "IO7_7") (pintype "bidirectional"))
      (node (ref "U3") (pin "5") (pinfunction "DI(IO0)_5") (pintype "bidirectional"))
    )
    (net (code "21") (name "Net-(CHG_LED-PadC)") (class "Default")
      (node (ref "CHG_LED") (pin "C") (pinfunction "C_C") (pintype "passive"))
      (node (ref "R1_BAT") (pin "1") (pinfunction "1_1") (pintype "passive"))
    )
    (net (code "22") (name "Net-(D2-CATHODE)") (class "Default")
      (node (ref "C1_BAT1") (pin "1") (pinfunction "1_1") (pintype "passive"))
      (node (ref "D2") (pin "1") (pinfunction "CATHODE_1") (pintype "bidirectional"))
      (node (ref "IC4") (pin "1") (pinfunction "VIN_1") (pintype "bidirectional"))
      (node (ref "IC4") (pin "3") (pinfunction "CE_3") (pintype "bidirectional"))
      (node (ref "Q1") (pin "2") (pinfunction "S_2") (pintype "bidirectional"))
    )
    (net (code "23") (name "Net-(D3-A)") (class "Default")
      (node (ref "C4") (pin "1") (pinfunction "1_1") (pintype "passive"))
      (node (ref "D3") (pin "2") (pinfunction "A_2") (pintype "bidirectional"))
      (node (ref "D4") (pin "1") (pinfunction "K_1") (pintype "bidirectional"))
    )
    (net (code "24") (name "Net-(D12-CATHODE)") (class "Default")
      (node (ref "D12") (pin "1") (pinfunction "CATHODE_1") (pintype "bidirectional"))
      (node (ref "R_CAPACITOR") (pin "1") (pinfunction "1_1") (pintype "passive"))
    )
    (net (code "25") (name "Net-(EPD_C1-Pad1)") (class "Default")
      (node (ref "EPD_C1") (pin "1") (pinfunction "1_1") (pintype "passive"))
      (node (ref "J1") (pin "4") (pinfunction "4_4") (pintype "bidirectional"))
    )
    (net (code "26") (name "Net-(EPD_C2-Pad1)") (class "Default")
      (node (ref "EPD_C2") (pin "1") (pinfunction "1_1") (pintype "passive"))
      (node (ref "J1") (pin "5") (pinfunction "5_5") (pintype "bidirectional"))
    )
    (net (code "27") (name "Net-(EPD_C6-Pad1)") (class "Default")
      (node (ref "EPD_C6") (pin "1") (pinfunction "1_1") (pintype "passive"))
      (node (ref "J1") (pin "18") (pinfunction "18_18") (pintype "bidirectional"))
    )
    (net (code "28") (name "Net-(EPD_C7-Pad1)") (class "Default")
      (node (ref "EPD_C7") (pin "1") (pinfunction "1_1") (pintype "passive"))
      (node (ref "J1") (pin "19") (pinfunction "19_19") (pintype "bidirectional"))
    )
    (net (code "29") (name "Net-(EPD_C8-Pad1)") (class "Default")
      (node (ref "EPD_C8") (pin "1") (pinfunction "1_1") (pintype "passive"))
      (node (ref "J1") (pin "20") (pinfunction "20_20") (pintype "bidirectional"))
    )
    (net (code "30") (name "Net-(EPD_C10-Pad1)") (class "Default")
      (node (ref "EPD_C10") (pin "1") (pinfunction "1_1") (pintype "passive"))
      (node (ref "J1") (pin "22") (pinfunction "22_22") (pintype "bidirectional"))
    )
    (net (code "31") (name "Net-(EPD_C12-Pad1)") (class "Default")
      (node (ref "EPD_C12") (pin "1") (pinfunction "1_1") (pintype "passive"))
      (node (ref "J1") (pin "24") (pinfunction "24_24") (pintype "bidirectional"))
    )
    (net (code "32") (name "Net-(IC1-CT)") (class "Default")
      (node (ref "C_DELAY") (pin "1") (pinfunction "1_1") (pintype "passive"))
      (node (ref "IC1") (pin "5") (pinfunction "CT_5") (pintype "bidirectional"))
    )
    (net (code "33") (name "Net-(J2-PadA5)") (class "Default")
      (node (ref "J2") (pin "A5") (pinfunction "A5_A5") (pintype "bidirectional"))
      (node (ref "R2-USB1") (pin "2") (pinfunction "2_2") (pintype "passive"))
    )
    (net (code "34") (name "Net-(J2-PadB5)") (class "Default")
      (node (ref "J2") (pin "B5") (pinfunction "B5_B5") (pintype "bidirectional"))
      (node (ref "R2-USB") (pin "1") (pinfunction "1_1") (pintype "passive"))
    )
    (net (code "35") (name "Net-(MCP73831-PROG)") (class "Default")
      (node (ref "MCP73831") (pin "5") (pinfunction "PROG_5") (pintype "input"))
      (node (ref "R2_BAT") (pin "2") (pinfunction "2_2") (pintype "passive"))
    )
    (net (code "36") (name "Net-(MCP73831-STAT)") (class "Default")
      (node (ref "MCP73831") (pin "1") (pinfunction "STAT_1") (pintype "output"))
      (node (ref "R1_BAT") (pin "2") (pinfunction "2_2") (pintype "passive"))
    )
    (net (code "37") (name "PREVGH") (class "Default")
      (node (ref "D5") (pin "1") (pinfunction "K_1") (pintype "bidirectional"))
      (node (ref "EPD_C9") (pin "1") (pinfunction "1_1") (pintype "passive"))
      (node (ref "J1") (pin "21") (pinfunction "21_21") (pintype "bidirectional"))
    )
    (net (code "38") (name "PREVGL") (class "Default")
      (node (ref "D4") (pin "2") (pinfunction "A_2") (pintype "bidirectional"))
      (node (ref "EPD_C11") (pin "1") (pinfunction "1_1") (pintype "passive"))
      (node (ref "J1") (pin "23") (pinfunction "23_23") (pintype "bidirectional"))
    )
    (net (code "39") (name "RESE") (class "Default")
      (node (ref "J1") (pin "3") (pinfunction "3_3") (pintype "bidirectional"))
      (node (ref "Q3") (pin "2") (pinfunction "S_2") (pintype "bidirectional"))
      (node (ref "R3") (pin "2") (pinfunction "2_2") (pintype "passive"))
    )
    (net (code "40") (name "RESE'") (class "Default")
      (node (ref "R2") (pin "2") (pinfunction "2_2") (pintype "passive"))
      (node (ref "R3") (pin "1") (pinfunction "1_1") (pintype "passive"))
      (node (ref "SJ1") (pin "2") (pinfunction "2_2") (pintype "passive"))
    )
    (net (code "41") (name "RESET") (class "Default")
      (node (ref "C5") (pin "1") (pinfunction "1_1") (pintype "passive"))
      (node (ref "IC1") (pin "1") (pinfunction "VOUT_1") (pintype "bidirectional"))
      (node (ref "RESET_BUTTON") (pin "3") (pinfunction "3_3") (pintype "passive"))
      (node (ref "RESET_BUTTON") (pin "4") (pinfunction "4_4") (pintype "passive"))
      (node (ref "R_RESET") (pin "1") (pinfunction "1_1") (pintype "passive"))
      (node (ref "U2") (pin "3") (pinfunction "EN_3") (pintype "input"))
    )
    (net (code "42") (name "RTC_RST") (class "Default")
      (node (ref "U2") (pin "16") (pinfunction "IO18_16") (pintype "bidirectional"))
      (node (ref "U4") (pin "4") (pinfunction "~{RST}_4") (pintype "input"))
    )
    (net (code "43") (name "RX") (class "Default")
      (node (ref "TP_RX") (pin "TP") (pinfunction "TP_TP") (pintype "input"))
      (node (ref "U2") (pin "24") (pinfunction "RXD0/GPIO17_24") (pintype "bidirectional"))
    )
    (net (code "44") (name "SCK") (class "Default")
      (node (ref "D8") (pin "2") (pinfunction "2_2") (pintype "passive"))
      (node (ref "J1") (pin "13") (pinfunction "13_13") (pintype "bidirectional"))
      (node (ref "J4") (pin "P5") (pinfunction "CLK_P5") (pintype "bidirectional"))
      (node (ref "R8") (pin "1") (pinfunction "1_1") (pintype "passive"))
      (node (ref "TP_SCK") (pin "TP") (pinfunction "TP_TP") (pintype "input"))
      (node (ref "U2") (pin "6") (pinfunction "IO6_6") (pintype "bidirectional"))
      (node (ref "U3") (pin "6") (pinfunction "CLK_6") (pintype "input"))
    )
    (net (code "45") (name "SCL") (class "Default")
      (node (ref "J3") (pin "4") (pinfunction "4_4") (pintype "passive"))
      (node (ref "R2_PINH") (pin "1") (pinfunction "1_1") (pintype "passive"))
      (node (ref "SENSOR2") (pin "4") (pinfunction "SCK_4") (pintype "input"))
      (node (ref "U1") (pin "7") (pinfunction "SCL_7") (pintype "input"))
      (node (ref "U2") (pin "20") (pinfunction "IO22_20") (pintype "bidirectional"))
      (node (ref "U4") (pin "16") (pinfunction "SCL_16") (pintype "input"))
    )
    (net (code "46") (name "SDA") (class "Default")
      (node (ref "J3") (pin "3") (pinfunction "3_3") (pintype "passive"))
      (node (ref "R1_PINH") (pin "1") (pinfunction "1_1") (pintype "passive"))
      (node (ref "SENSOR2") (pin "3") (pinfunction "SDI_3") (pintype "bidirectional"))
      (node (ref "U1") (pin "8") (pinfunction "SDA_8") (pintype "bidirectional"))
      (node (ref "U2") (pin "19") (pinfunction "IO21_19") (pintype "bidirectional"))
      (node (ref "U4") (pin "15") (pinfunction "SDA_15") (pintype "bidirectional"))
    )
    (net (code "47") (name "SRC") (class "Default")
      (node (ref "C4") (pin "2") (pinfunction "2_2") (pintype "passive"))
      (node (ref "D5") (pin "2") (pinfunction "A_2") (pintype "bidirectional"))
      (node (ref "L1") (pin "1") (pinfunction "1_1") (pintype "passive"))
      (node (ref "Q3") (pin "3") (pinfunction "D_3") (pintype "bidirectional"))
    )
    (net (code "48") (name "SS_SD") (class "Default")
      (node (ref "D11") (pin "2") (pinfunction "2_2") (pintype "passive"))
      (node (ref "J4") (pin "P2") (pinfunction "CD/DAT3_P2") (pintype "bidirectional"))
      (node (ref "R11") (pin "1") (pinfunction "1_1") (pintype "passive"))
      (node (ref "U2") (pin "4") (pinfunction "IO4_4") (pintype "bidirectional"))
    )
    (net (code "49") (name "TX") (class "Default")
      (node (ref "TP_TX") (pin "TP") (pinfunction "TP_TP") (pintype "input"))
      (node (ref "U2") (pin "25") (pinfunction "TXD0/GPIO16_25") (pintype "bidirectional"))
    )
    (net (code "50") (name "USB_D+") (class "Default")
      (node (ref "D1") (pin "1") (pinfunction "I/O1_1_1") (pintype "bidirectional"))
      (node (ref "U2") (pin "14") (pinfunction "IO13_14") (pintype "bidirectional"))
    )
    (net (code "51") (name "USB_D-") (class "Default")
      (node (ref "D1") (pin "3") (pinfunction "I/O2_1_3") (pintype "bidirectional"))
      (node (ref "U2") (pin "13") (pinfunction "IO12_13") (pintype "bidirectional"))
    )
    (net (code "52") (name "VBAT") (class "Default")
      (node (ref "C2_BAT") (pin "1") (pinfunction "1_1") (pintype "passive"))
      (node (ref "MCP73831") (pin "3") (pinfunction "VBAT_3") (pintype "power_in"))
      (node (ref "Q1") (pin "3") (pinfunction "D_3") (pintype "bidirectional"))
      (node (ref "TP_VBAT") (pin "TP") (pinfunction "TP_TP") (pintype "input"))
      (node (ref "U1") (pin "2") (pinfunction "CELL_2") (pintype "power_in"))
      (node (ref "U1") (pin "3") (pinfunction "VDD_3") (pintype "power_in"))
    )
    (net (code "53") (name "VBUS") (class "Default")
      (node (ref "C1_BAT") (pin "1") (pinfunction "1_1") (pintype "passive"))
      (node (ref "C4_USB") (pin "1") (pinfunction "1_1") (pintype "passive"))
      (node (ref "C5_USB") (pin "1") (pinfunction "1_1") (pintype "passive"))
      (node (ref "CHG_LED") (pin "A") (pinfunction "A_A") (pintype "passive"))
      (node (ref "D1") (pin "5") (pinfunction "VBUS_5") (pintype "bidirectional"))
      (node (ref "D2") (pin "2") (pinfunction "ANODE_2") (pintype "bidirectional"))
      (node (ref "MCP73831") (pin "4") (pinfunction "VIN_4") (pintype "power_in"))
      (node (ref "PFMF.050.1") (pin "2") (pinfunction "2_2") (pintype "passive"))
      (node (ref "Q1") (pin "1") (pinfunction "G_1") (pintype "bidirectional"))
      (node (ref "R1") (pin "2") (pinfunction "2_2") (pintype "passive"))
      (node (ref "TP_VBUS") (pin "TP") (pinfunction "TP_TP") (pintype "input"))
    )
    (net (code "54") (name "VRTC") (class "Default")
      (node (ref "C10_SUPERCAP") (pin "2") (pinfunction "2_2") (pintype "passive"))
      (node (ref "C11") (pin "1") (pinfunction "1_1") (pintype "passive"))
      (node (ref "R_CAPACITOR") (pin "2") (pinfunction "2_2") (pintype "passive"))
      (node (ref "U4") (pin "14") (pinfunction "VBAT_14") (pintype "power_in"))
    )
    (net (code "55") (name "VUSB") (class "Default")
      (node (ref "J2") (pin "A4") (pinfunction "A4_A4") (pintype "bidirectional"))
      (node (ref "J2") (pin "A9") (pinfunction "A9_A9") (pintype "bidirectional"))
      (node (ref "J2") (pin "B4") (pinfunction "B4_B4") (pintype "bidirectional"))
      (node (ref "J2") (pin "B9") (pinfunction "B9_B9") (pintype "bidirectional"))
      (node (ref "PFMF.050.1") (pin "1") (pinfunction "1_1") (pintype "passive"))
    )
    (net (code "56") (name "unconnected-(IC1-NC-Pad4)") (class "Default")
      (node (ref "IC1") (pin "4") (pinfunction "NC_4") (pintype "no_connect"))
    )
    (net (code "57") (name "unconnected-(IC4-NC-Pad4)") (class "Default")
      (node (ref "IC4") (pin "4") (pinfunction "NC_4") (pintype "no_connect"))
    )
    (net (code "58") (name "unconnected-(J1-Pad1)") (class "Default")
      (node (ref "J1") (pin "1") (pinfunction "1_1") (pintype "bidirectional"))
    )
    (net (code "59") (name "unconnected-(J1-Pad6)") (class "Default")
      (node (ref "J1") (pin "6") (pinfunction "6_6") (pintype "bidirectional"))
    )
    (net (code "60") (name "unconnected-(J1-Pad7)") (class "Default")
      (node (ref "J1") (pin "7") (pinfunction "7_7") (pintype "bidirectional"))
    )
    (net (code "61") (name "unconnected-(J2-PadA8)") (class "Default")
      (node (ref "J2") (pin "A8") (pinfunction "A8_A8") (pintype "bidirectional"))
    )
    (net (code "62") (name "unconnected-(J2-PadB8)") (class "Default")
      (node (ref "J2") (pin "B8") (pinfunction "B8_B8") (pintype "bidirectional"))
    )
    (net (code "63") (name "unconnected-(J4-DAT1-PadP8)") (class "Default")
      (node (ref "J4") (pin "P8") (pinfunction "DAT1_P8") (pintype "bidirectional"))
    )
    (net (code "64") (name "unconnected-(J4-DAT2-PadP1)") (class "Default")
      (node (ref "J4") (pin "P1") (pinfunction "DAT2_P1") (pintype "bidirectional"))
    )
    (net (code "65") (name "unconnected-(J4-DETECTION_1-PadS1)") (class "Default")
      (node (ref "J4") (pin "S1") (pinfunction "DETECTION_1_S1") (pintype "bidirectional"))
    )
    (net (code "66") (name "unconnected-(J4-DETECTION_2-PadS2)") (class "Default")
      (node (ref "J4") (pin "S2") (pinfunction "DETECTION_2_S2") (pintype "bidirectional"))
    )
    (net (code "67") (name "unconnected-(U1-~{ALERT}-Pad5)") (class "Default")
      (node (ref "U1") (pin "5") (pinfunction "~{ALERT}_5") (pintype "output"))
    )
    (net (code "68") (name "unconnected-(U2-NC-Pad22)") (class "Default")
      (node (ref "U2") (pin "22") (pinfunction "NC_22") (pintype "no_connect"))
    )
  )
)
